# Arduino_uno_sch.net
KiCad netlist of a schematic drawn in Altium Designer
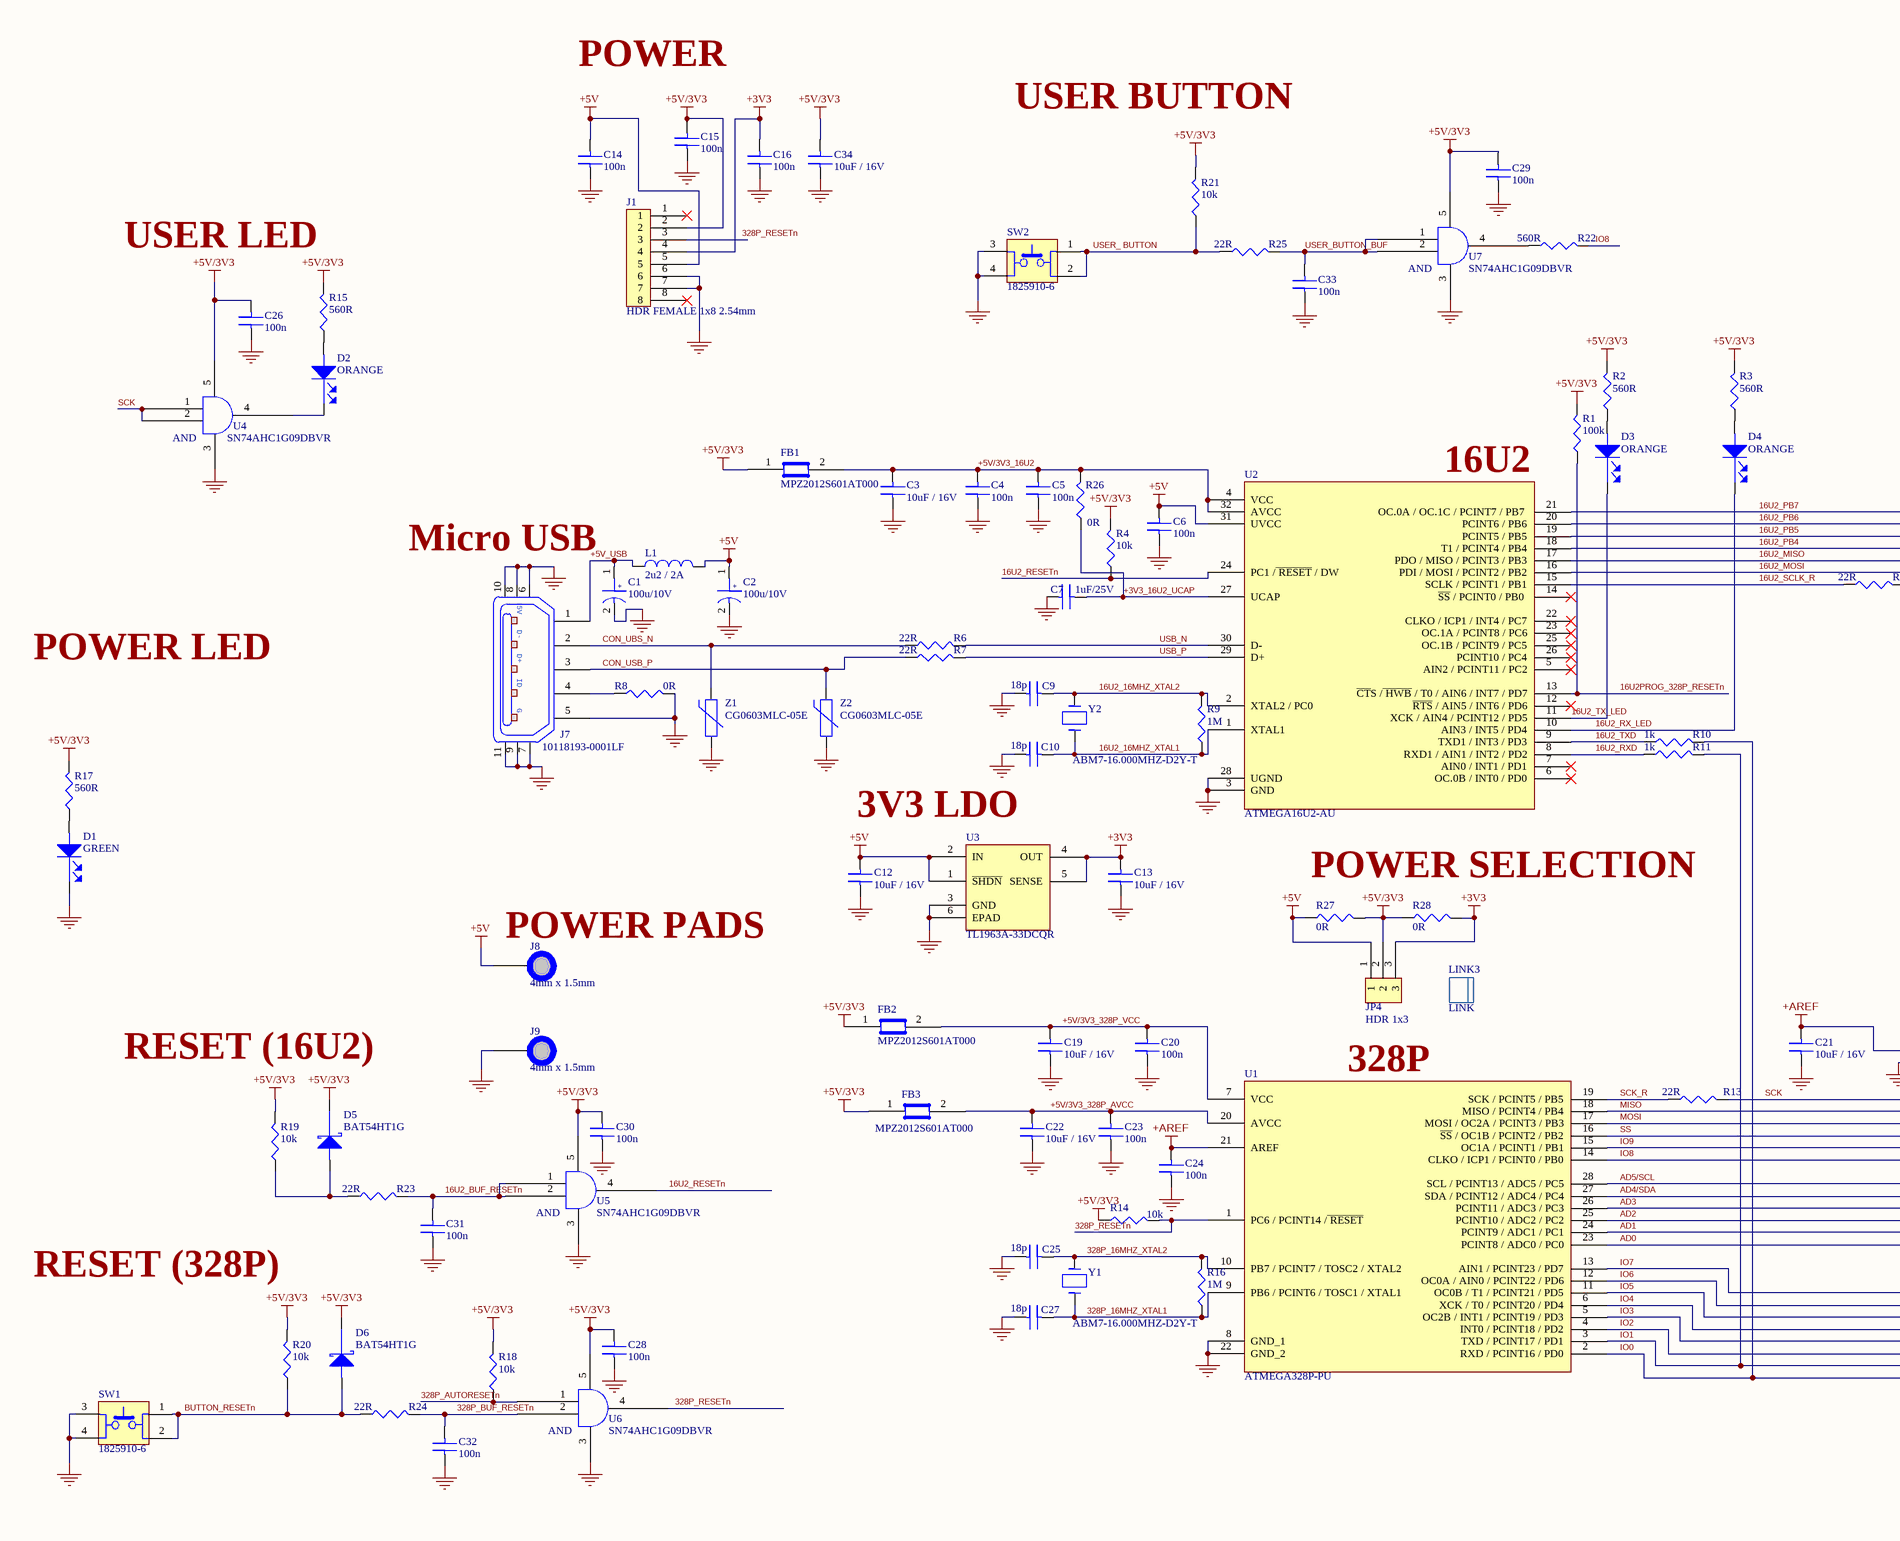
[diagram p0: Arduino_uno_sch.SchDoc, left]
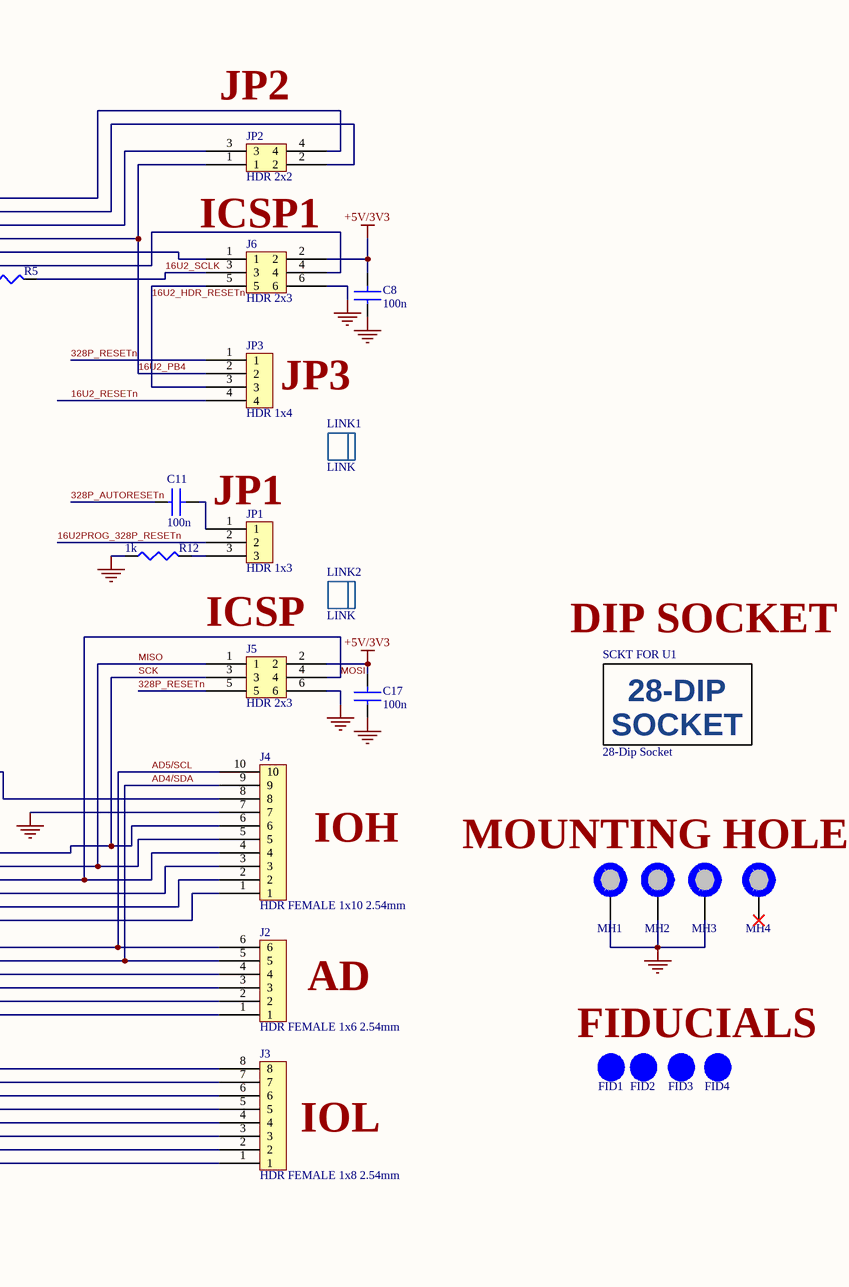
[diagram p1: Arduino_uno_sch.SchDoc, right]

(export (version "E")
  (design (tool "Eeschema 10.0.6"))
  (components
    (comp (ref "C1")
      (value "100u/10V")
      (footprint "C_ALU_C_SIZE")
      (description "Cap Aluminum 100uF 10V 20% (5 X 5.4mm) SMD 50mA 1000 hr 85°C T/R")
      (fields
        (field (name "MANUFACTURER") "Panasonic")
        (field (name "MANUFACTURER PART NUMBER") "EEE-1AA101WR")
      )
      (libsource (lib "Arduino_Schlib1") (part "EEE-1AA101WR"))
    )
    (comp (ref "C2")
      (value "100u/10V")
      (footprint "C_ALU_C_SIZE")
      (description "Cap Aluminum 100uF 10V 20% (5 X 5.4mm) SMD 50mA 1000 hr 85°C T/R")
      (fields
        (field (name "MANUFACTURER") "Panasonic")
        (field (name "MANUFACTURER PART NUMBER") "EEE-1AA101WR")
      )
      (libsource (lib "Arduino_Schlib1") (part "EEE-1AA101WR"))
    )
    (comp (ref "C3")
      (value "10uF / 16V")
      (footprint "C0805")
      (fields
        (field (name "MANUFACTURER") "TDK")
        (field (name "MANUFACTURER PART NUMBER") "C2012X5R1C106M125AC")
        (field (name "TOLERANCE") "20%")
      )
      (libsource (lib "Arduino_Schlib1") (part "C2012X5R1C106M125AC"))
    )
    (comp (ref "C4")
      (value "100n")
      (footprint "C0805")
      (fields
        (field (name "MANUFACTURER") "TDK")
        (field (name "MANUFACTURER PART NUMBER") "C2012X7R1H104K085AA")
        (field (name "TOLERANCE") "10%")
      )
      (libsource (lib "Arduino_Schlib1") (part "C2012X7R1H104K085AA"))
    )
    (comp (ref "C5")
      (value "100n")
      (footprint "C0805")
      (fields
        (field (name "MANUFACTURER") "TDK")
        (field (name "MANUFACTURER PART NUMBER") "C2012X7R1H104K085AA")
        (field (name "TOLERANCE") "10%")
      )
      (libsource (lib "Arduino_Schlib1") (part "C2012X7R1H104K085AA"))
    )
    (comp (ref "C6")
      (value "100n")
      (footprint "C0805")
      (fields
        (field (name "MANUFACTURER") "TDK")
        (field (name "MANUFACTURER PART NUMBER") "C2012X7R1H104K085AA")
        (field (name "TOLERANCE") "10%")
      )
      (libsource (lib "Arduino_Schlib1") (part "C2012X7R1H104K085AA"))
    )
    (comp (ref "C7")
      (value "1uF/25V")
      (footprint "C0805")
      (fields
        (field (name "MANUFACTURER") "TDK")
        (field (name "MANUFACTURER PART NUMBER") "C2012X5R1E105K125AA")
        (field (name "VOLTAGE") "25V")
      )
      (libsource (lib "Arduino_Schlib1") (part "C2012X5R1E105K125AA"))
    )
    (comp (ref "C8")
      (value "100n")
      (footprint "C0805")
      (fields
        (field (name "MANUFACTURER") "TDK")
        (field (name "MANUFACTURER PART NUMBER") "C2012X7R1H104K085AA")
        (field (name "TOLERANCE") "10%")
      )
      (libsource (lib "Arduino_Schlib1") (part "C2012X7R1H104K085AA"))
    )
    (comp (ref "C9")
      (value "18p")
      (footprint "C0805")
      (description "CAP CER 18PF 50V C0G/NP0 0805")
      (fields
        (field (name "MANUFACTURER") "KEMET")
        (field (name "MANUFACTURER PART NUMBER") "C0805C180J5GACTU")
      )
      (libsource (lib "Arduino_Schlib1") (part "C0805C180J5GACTU"))
    )
    (comp (ref "C10")
      (value "18p")
      (footprint "C0805")
      (description "CAP CER 18PF 50V C0G/NP0 0805")
      (fields
        (field (name "MANUFACTURER") "KEMET")
        (field (name "MANUFACTURER PART NUMBER") "C0805C180J5GACTU")
      )
      (libsource (lib "Arduino_Schlib1") (part "C0805C180J5GACTU"))
    )
    (comp (ref "C11")
      (value "100n")
      (footprint "C0805")
      (fields
        (field (name "MANUFACTURER") "TDK")
        (field (name "MANUFACTURER PART NUMBER") "C2012X7R1H104K085AA")
        (field (name "TOLERANCE") "10%")
      )
      (libsource (lib "Arduino_Schlib1") (part "C2012X7R1H104K085AA"))
    )
    (comp (ref "C12")
      (value "10uF / 16V")
      (footprint "C0805")
      (fields
        (field (name "MANUFACTURER") "TDK")
        (field (name "MANUFACTURER PART NUMBER") "C2012X5R1C106M125AC")
        (field (name "TOLERANCE") "20%")
      )
      (libsource (lib "Arduino_Schlib1") (part "C2012X5R1C106M125AC"))
    )
    (comp (ref "C13")
      (value "10uF / 16V")
      (footprint "C0805")
      (fields
        (field (name "MANUFACTURER") "TDK")
        (field (name "MANUFACTURER PART NUMBER") "C2012X5R1C106M125AC")
        (field (name "TOLERANCE") "20%")
      )
      (libsource (lib "Arduino_Schlib1") (part "C2012X5R1C106M125AC"))
    )
    (comp (ref "C14")
      (value "100n")
      (footprint "C0805")
      (fields
        (field (name "MANUFACTURER") "TDK")
        (field (name "MANUFACTURER PART NUMBER") "C2012X7R1H104K085AA")
        (field (name "TOLERANCE") "10%")
      )
      (libsource (lib "Arduino_Schlib1") (part "C2012X7R1H104K085AA"))
    )
    (comp (ref "C15")
      (value "100n")
      (footprint "C0805")
      (fields
        (field (name "MANUFACTURER") "TDK")
        (field (name "MANUFACTURER PART NUMBER") "C2012X7R1H104K085AA")
        (field (name "TOLERANCE") "10%")
      )
      (libsource (lib "Arduino_Schlib1") (part "C2012X7R1H104K085AA"))
    )
    (comp (ref "C16")
      (value "100n")
      (footprint "C0805")
      (fields
        (field (name "MANUFACTURER") "TDK")
        (field (name "MANUFACTURER PART NUMBER") "C2012X7R1H104K085AA")
        (field (name "TOLERANCE") "10%")
      )
      (libsource (lib "Arduino_Schlib1") (part "C2012X7R1H104K085AA"))
    )
    (comp (ref "C17")
      (value "100n")
      (footprint "C0805")
      (fields
        (field (name "MANUFACTURER") "TDK")
        (field (name "MANUFACTURER PART NUMBER") "C2012X7R1H104K085AA")
        (field (name "TOLERANCE") "10%")
      )
      (libsource (lib "Arduino_Schlib1") (part "C2012X7R1H104K085AA"))
    )
    (comp (ref "C19")
      (value "10uF / 16V")
      (footprint "C0805")
      (fields
        (field (name "MANUFACTURER") "TDK")
        (field (name "MANUFACTURER PART NUMBER") "C2012X5R1C106M125AC")
        (field (name "TOLERANCE") "20%")
      )
      (libsource (lib "Arduino_Schlib1") (part "C2012X5R1C106M125AC"))
    )
    (comp (ref "C20")
      (value "100n")
      (footprint "C0805")
      (fields
        (field (name "MANUFACTURER") "TDK")
        (field (name "MANUFACTURER PART NUMBER") "C2012X7R1H104K085AA")
        (field (name "TOLERANCE") "10%")
      )
      (libsource (lib "Arduino_Schlib1") (part "C2012X7R1H104K085AA"))
    )
    (comp (ref "C21")
      (value "10uF / 16V")
      (footprint "C0805")
      (fields
        (field (name "MANUFACTURER") "TDK")
        (field (name "MANUFACTURER PART NUMBER") "C2012X5R1C106M125AC")
        (field (name "TOLERANCE") "20%")
      )
      (libsource (lib "Arduino_Schlib1") (part "C2012X5R1C106M125AC"))
    )
    (comp (ref "C22")
      (value "10uF / 16V")
      (footprint "C0805")
      (fields
        (field (name "MANUFACTURER") "TDK")
        (field (name "MANUFACTURER PART NUMBER") "C2012X5R1C106M125AC")
        (field (name "TOLERANCE") "20%")
      )
      (libsource (lib "Arduino_Schlib1") (part "C2012X5R1C106M125AC"))
    )
    (comp (ref "C23")
      (value "100n")
      (footprint "C0805")
      (fields
        (field (name "MANUFACTURER") "TDK")
        (field (name "MANUFACTURER PART NUMBER") "C2012X7R1H104K085AA")
        (field (name "TOLERANCE") "10%")
      )
      (libsource (lib "Arduino_Schlib1") (part "C2012X7R1H104K085AA"))
    )
    (comp (ref "C24")
      (value "100n")
      (footprint "C0805")
      (fields
        (field (name "MANUFACTURER") "TDK")
        (field (name "MANUFACTURER PART NUMBER") "C2012X7R1H104K085AA")
        (field (name "TOLERANCE") "10%")
      )
      (libsource (lib "Arduino_Schlib1") (part "C2012X7R1H104K085AA"))
    )
    (comp (ref "C25")
      (value "18p")
      (footprint "C0805")
      (description "CAP CER 18PF 50V C0G/NP0 0805")
      (fields
        (field (name "MANUFACTURER") "KEMET")
        (field (name "MANUFACTURER PART NUMBER") "C0805C180J5GACTU")
      )
      (libsource (lib "Arduino_Schlib1") (part "C0805C180J5GACTU"))
    )
    (comp (ref "C26")
      (value "100n")
      (footprint "C0805")
      (fields
        (field (name "MANUFACTURER") "TDK")
        (field (name "MANUFACTURER PART NUMBER") "C2012X7R1H104K085AA")
        (field (name "TOLERANCE") "10%")
      )
      (libsource (lib "Arduino_Schlib1") (part "C2012X7R1H104K085AA"))
    )
    (comp (ref "C27")
      (value "18p")
      (footprint "C0805")
      (description "CAP CER 18PF 50V C0G/NP0 0805")
      (fields
        (field (name "MANUFACTURER") "KEMET")
        (field (name "MANUFACTURER PART NUMBER") "C0805C180J5GACTU")
      )
      (libsource (lib "Arduino_Schlib1") (part "C0805C180J5GACTU"))
    )
    (comp (ref "C28")
      (value "100n")
      (footprint "C0805")
      (fields
        (field (name "MANUFACTURER") "TDK")
        (field (name "MANUFACTURER PART NUMBER") "C2012X7R1H104K085AA")
        (field (name "TOLERANCE") "10%")
      )
      (libsource (lib "Arduino_Schlib1") (part "C2012X7R1H104K085AA"))
    )
    (comp (ref "C29")
      (value "100n")
      (footprint "C0805")
      (fields
        (field (name "MANUFACTURER") "TDK")
        (field (name "MANUFACTURER PART NUMBER") "C2012X7R1H104K085AA")
        (field (name "TOLERANCE") "10%")
      )
      (libsource (lib "Arduino_Schlib1") (part "C2012X7R1H104K085AA"))
    )
    (comp (ref "C30")
      (value "100n")
      (footprint "C0805")
      (fields
        (field (name "MANUFACTURER") "TDK")
        (field (name "MANUFACTURER PART NUMBER") "C2012X7R1H104K085AA")
        (field (name "TOLERANCE") "10%")
      )
      (libsource (lib "Arduino_Schlib1") (part "C2012X7R1H104K085AA"))
    )
    (comp (ref "C31")
      (value "100n")
      (footprint "C0805")
      (fields
        (field (name "MANUFACTURER") "TDK")
        (field (name "MANUFACTURER PART NUMBER") "C2012X7R1H104K085AA")
        (field (name "TOLERANCE") "10%")
      )
      (libsource (lib "Arduino_Schlib1") (part "C2012X7R1H104K085AA"))
    )
    (comp (ref "C32")
      (value "100n")
      (footprint "C0805")
      (fields
        (field (name "MANUFACTURER") "TDK")
        (field (name "MANUFACTURER PART NUMBER") "C2012X7R1H104K085AA")
        (field (name "TOLERANCE") "10%")
      )
      (libsource (lib "Arduino_Schlib1") (part "C2012X7R1H104K085AA"))
    )
    (comp (ref "C33")
      (value "100n")
      (footprint "C0805")
      (fields
        (field (name "MANUFACTURER") "TDK")
        (field (name "MANUFACTURER PART NUMBER") "C2012X7R1H104K085AA")
        (field (name "TOLERANCE") "10%")
      )
      (libsource (lib "Arduino_Schlib1") (part "C2012X7R1H104K085AA"))
    )
    (comp (ref "C34")
      (value "10uF / 16V")
      (footprint "C0805")
      (fields
        (field (name "MANUFACTURER") "TDK")
        (field (name "MANUFACTURER PART NUMBER") "C2012X5R1C106M125AC")
        (field (name "TOLERANCE") "20%")
      )
      (libsource (lib "Arduino_Schlib1") (part "C2012X5R1C106M125AC"))
    )
    (comp (ref "D1")
      (value "GREEN")
      (footprint "LED0603")
      (description "LED Uni-Color Green 572nm 2-Pin Chip 0603(1608Metric) T/R")
      (fields
        (field (name "MANUFACTURER") "Osram Opto")
        (field (name "MANUFACTURER PART NUMBER") "LGL29K-G2J1-24-Z")
      )
      (libsource (lib "Arduino_Schlib1") (part "LGL29K-G2J1-24-Z"))
    )
    (comp (ref "D2")
      (value "ORANGE")
      (footprint "LED0603")
      (description "OSRAM - LO L29K-H2K1-24-Z - SMARTLED 0603 ORANGE")
      (fields
        (field (name "MANUFACTURER") "Osram Opto")
        (field (name "MANUFACTURER PART NUMBER") "LOL29K-H2K1-24-Z")
      )
      (libsource (lib "Arduino_Schlib1") (part "LOL29K-H2K1-24-Z"))
    )
    (comp (ref "D3")
      (value "ORANGE")
      (footprint "LED0603")
      (description "OSRAM - LO L29K-H2K1-24-Z - SMARTLED 0603 ORANGE")
      (fields
        (field (name "MANUFACTURER") "Osram Opto")
        (field (name "MANUFACTURER PART NUMBER") "LOL29K-H2K1-24-Z")
      )
      (libsource (lib "Arduino_Schlib1") (part "LOL29K-H2K1-24-Z"))
    )
    (comp (ref "D4")
      (value "ORANGE")
      (footprint "LED0603")
      (description "OSRAM - LO L29K-H2K1-24-Z - SMARTLED 0603 ORANGE")
      (fields
        (field (name "MANUFACTURER") "Osram Opto")
        (field (name "MANUFACTURER PART NUMBER") "LOL29K-H2K1-24-Z")
      )
      (libsource (lib "Arduino_Schlib1") (part "LOL29K-H2K1-24-Z"))
    )
    (comp (ref "D5")
      (value "BAT54HT1G")
      (footprint "SOD323")
      (description "Small Signal Schottky Diode, Single, 30 V, 200 mA, 800 mV, 600 mA, 150 C ;RoHS Compliant: Yes")
      (fields (field (name "MANUFACTURER") "ON Semiconductor / Fairchild"))
      (libsource (lib "Arduino_Schlib1") (part "BAT54HT1G"))
    )
    (comp (ref "D6")
      (value "BAT54HT1G")
      (footprint "SOD323")
      (description "Small Signal Schottky Diode, Single, 30 V, 200 mA, 800 mV, 600 mA, 150 C ;RoHS Compliant: Yes")
      (fields (field (name "MANUFACTURER") "ON Semiconductor / Fairchild"))
      (libsource (lib "Arduino_Schlib1") (part "BAT54HT1G"))
    )
    (comp (ref "FB1")
      (value "MPZ2012S601AT000")
      (footprint "C0805")
      (description "FERRITE BEAD 600 OHM 0805 1LN")
      (fields (field (name "MANUFACTURER") "TDK"))
      (libsource (lib "Arduino_Schlib1") (part "MPZ2012S601AT000"))
    )
    (comp (ref "FB2")
      (value "MPZ2012S601AT000")
      (footprint "C0805")
      (description "FERRITE BEAD 600 OHM 0805 1LN")
      (fields (field (name "MANUFACTURER") "TDK"))
      (libsource (lib "Arduino_Schlib1") (part "MPZ2012S601AT000"))
    )
    (comp (ref "FB3")
      (value "MPZ2012S601AT000")
      (footprint "C0805")
      (description "FERRITE BEAD 600 OHM 0805 1LN")
      (fields (field (name "MANUFACTURER") "TDK"))
      (libsource (lib "Arduino_Schlib1") (part "MPZ2012S601AT000"))
    )
    (comp (ref "FID1")
      (value "FID_1MMC")
      (footprint "FID _40X120D")
      (description "Fiducial 40 mil diameter, 120 mil mask")
      (libsource (lib "Arduino_Schlib1") (part "FID_1MMC"))
    )
    (comp (ref "FID2")
      (value "FID_1MMC")
      (footprint "FID _40X120D")
      (description "Fiducial 40 mil diameter, 120 mil mask")
      (libsource (lib "Arduino_Schlib1") (part "FID_1MMC"))
    )
    (comp (ref "FID3")
      (value "FID_1MMC")
      (footprint "FID _40X120D")
      (description "Fiducial 40 mil diameter, 120 mil mask")
      (libsource (lib "Arduino_Schlib1") (part "FID_1MMC"))
    )
    (comp (ref "FID4")
      (value "FID_1MMC")
      (footprint "FID _40X120D")
      (description "Fiducial 40 mil diameter, 120 mil mask")
      (libsource (lib "Arduino_Schlib1") (part "FID_1MMC"))
    )
    (comp (ref "J1")
      (value "HDR FEMALE 1x8 2.54mm")
      (footprint "Hdr_Female_1x8_2.54mm")
      (description "2.54mm (0.1\") Pitch SIL Vertical PC Tail Socket Assembly, selective gold + tin, 8 contacts")
      (fields (field (name "MANUFACTURER") "Harwin") (field (name "MANUFACTURER PART NUMBER") "M20-7820842"))
      (libsource (lib "") (part "M20-7820842_1"))
    )
    (comp (ref "J2")
      (value "HDR FEMALE 1x6 2.54mm")
      (footprint "Hdr_Female_1x6_2.54mm")
      (description "06-WAY SIL VERT SOCKET L/FREE")
      (fields (field (name "MANUFACTURER") "Harwin") (field (name "MANUFACTURER PART NUMBER") "M20-7820646"))
      (libsource (lib "Arduino_Schlib1") (part "M20-7820646"))
    )
    (comp (ref "J3")
      (value "HDR FEMALE 1x8 2.54mm")
      (footprint "Hdr_Female_1x8_2.54mm")
      (description "2.54mm (0.1\") Pitch SIL Vertical PC Tail Socket Assembly, selective gold + tin, 8 contacts")
      (fields (field (name "MANUFACTURER") "Harwin") (field (name "MANUFACTURER PART NUMBER") "M20-7820842"))
      (libsource (lib "Arduino_Schlib1") (part "M20-7820842"))
    )
    (comp (ref "J4")
      (value "HDR FEMALE 1x10 2.54mm")
      (footprint "Hdr_Female_1x10_2.54mm")
      (fields (field (name "MANUFACTURER") "Harwin") (field (name "MANUFACTURER PART NUMBER") "M20-7821046"))
      (libsource (lib "Arduino_Schlib1") (part "M20-7821046"))
    )
    (comp (ref "J5")
      (value "HDR 2x3")
      (footprint "HDR_2x3_2.54mm")
      (description "CONN HEADER 6POS .100 STR 30AU")
      (fields
        (field (name "MANUFACTURER") "Amphenol FCI")
        (field (name "MANUFACTURER PART NUMBER") "67997-106HLF")
      )
      (libsource (lib "Arduino_Schlib1") (part "67997-106HLF"))
    )
    (comp (ref "J6")
      (value "HDR 2x3")
      (footprint "HDR_2x3_2.54mm")
      (description "CONN HEADER 6POS .100 STR 30AU")
      (fields
        (field (name "MANUFACTURER") "Amphenol FCI")
        (field (name "MANUFACTURER PART NUMBER") "67997-106HLF")
      )
      (libsource (lib "Arduino_Schlib1") (part "67997-106HLF"))
    )
    (comp (ref "J7")
      (value "10118193-0001LF")
      (footprint "10118193")
      (description "CONN USB MICRO B RECPT SMT R/A")
      (fields (field (name "MANUFACTURER") "Amphenol FCI"))
      (libsource (lib "Arduino_Schlib1") (part "10118193-0001LF"))
    )
    (comp (ref "J8")
      (value "4mm x 1.5mm")
      (footprint "PAD_WITH_HOLE_4mm x 1.5mm")
      (description "Pad with a hole 4mm x 1.5mm")
      (libsource (lib "Arduino_Schlib1") (part "PAD_WITH_HOLE_4MMX1.5MM"))
    )
    (comp (ref "J9")
      (value "4mm x 1.5mm")
      (footprint "PAD_WITH_HOLE_4mm x 1.5mm")
      (description "Pad with a hole 4mm x 1.5mm")
      (libsource (lib "Arduino_Schlib1") (part "PAD_WITH_HOLE_4MMX1.5MM"))
    )
    (comp (ref "JP1")
      (value "HDR 1x3")
      (footprint "Hdr_Female_1x3_2.54mm")
      (description "Conn Unshrouded Header HDR 3 POS 2.54mm Solder ST Thru-Hole Bulk")
      (fields
        (field (name "MANUFACTURER") "Amphenol FCI")
        (field (name "MANUFACTURER PART NUMBER") "68000-103HLF")
      )
      (libsource (lib "Arduino_Schlib1") (part "68000-103HLF"))
    )
    (comp (ref "JP2")
      (value "HDR 2x2")
      (footprint "HDR_2x2_2.54mm")
      (description "CONN HEADER VERT 4POS 2.54MM")
      (fields
        (field (name "MANUFACTURER") "Amphenol FCI")
        (field (name "MANUFACTURER PART NUMBER") "68602-204HLF")
      )
      (libsource (lib "Arduino_Schlib1") (part "68602-204HLF"))
    )
    (comp (ref "JP3")
      (value "HDR 1x4")
      (footprint "Hdr_Female_1x4_2.54mm")
      (description "CONN HEADER VERT 4POS 2.54MM")
      (fields
        (field (name "MANUFACTURER") "Amphenol FCI")
        (field (name "MANUFACTURER PART NUMBER") "68001-204HLF")
      )
      (libsource (lib "Arduino_Schlib1") (part "68001-204HLF"))
    )
    (comp (ref "JP4")
      (value "HDR 1x3")
      (footprint "Hdr_Female_1x3_2.54mm")
      (description "Conn Unshrouded Header HDR 3 POS 2.54mm Solder ST Thru-Hole Bulk")
      (fields
        (field (name "MANUFACTURER") "Amphenol FCI")
        (field (name "MANUFACTURER PART NUMBER") "68000-103HLF")
      )
      (libsource (lib "") (part "68000-103HLF_1"))
    )
    (comp (ref "L1")
      (value "2u2 / 2A")
      (footprint "CL210_IND")
      (description "FIXED IND 2.2UH 2A 80 MOHM SMD")
      (fields
        (field (name "MANUFACTURER") "KEMET")
        (field (name "MANUFACTURER PART NUMBER") "L1210R2R2MDWIT")
      )
      (libsource (lib "Arduino_Schlib1") (part "L1210R2R2MDWIT"))
    )
    (comp (ref "LINK1")
      (value "LINK")
      (description "CONN JUMPER SHORTING .100\" GOLD")
      (fields
        (field (name "MANUFACTURER") "Sullins")
        (field (name "MANUFACTURER PART NUMBER") "QPC02SXGN-RC")
      )
      (libsource (lib "Arduino_Schlib1") (part "QPC02SXGN-RC"))
    )
    (comp (ref "LINK2")
      (value "LINK")
      (description "CONN JUMPER SHORTING .100\" GOLD")
      (fields
        (field (name "MANUFACTURER") "Sullins")
        (field (name "MANUFACTURER PART NUMBER") "QPC02SXGN-RC")
      )
      (libsource (lib "Arduino_Schlib1") (part "QPC02SXGN-RC"))
    )
    (comp (ref "LINK3")
      (value "LINK")
      (description "CONN JUMPER SHORTING .100\" GOLD")
      (fields
        (field (name "MANUFACTURER") "Sullins")
        (field (name "MANUFACTURER PART NUMBER") "QPC02SXGN-RC")
      )
      (libsource (lib "Arduino_Schlib1") (part "QPC02SXGN-RC"))
    )
    (comp (ref "MH1")
      (value "MH_7.4MMNC_3.2MMND")
      (footprint "MH_7.4MMNC_3.2MMND")
      (description "Hole 7.4mm diameter (Non copper) , 3.2mm drill NPTH")
      (libsource (lib "Arduino_Schlib1") (part "MH_7.4MMNC_3.2MMND"))
    )
    (comp (ref "MH2")
      (value "MH_7.4MMNC_3.2MMND")
      (footprint "MH_7.4MMNC_3.2MMND")
      (description "Hole 7.4mm diameter (Non copper) , 3.2mm drill NPTH")
      (libsource (lib "Arduino_Schlib1") (part "MH_7.4MMNC_3.2MMND"))
    )
    (comp (ref "MH3")
      (value "MH_7.4MMNC_3.2MMND")
      (footprint "MH_7.4MMNC_3.2MMND")
      (description "Hole 7.4mm diameter (Non copper) , 3.2mm drill NPTH")
      (libsource (lib "Arduino_Schlib1") (part "MH_7.4MMNC_3.2MMND"))
    )
    (comp (ref "MH4")
      (value "MH_7.4MMNC_3.2MMND")
      (footprint "MH_7.4MMNC_3.2MMND")
      (description "Hole 7.4mm diameter (Non copper) , 3.2mm drill NPTH")
      (libsource (lib "Arduino_Schlib1") (part "MH_7.4MMNC_3.2MMND"))
    )
    (comp (ref "R1")
      (value "100k")
      (footprint "R0805")
      (description "YAGEO         RC0805FR-07100KL            RES, THICK FILM, 100K, 1%, 0.125W, 0805, REEL")
      (fields
        (field (name "MANUFACTURER") "Yageo")
        (field (name "MANUFACTURER PART NUMBER") "RC0805FR-07100KL")
      )
      (libsource (lib "Arduino_Schlib1") (part "RC0805FR-07100KL"))
    )
    (comp (ref "R2")
      (value "560R")
      (footprint "R0805")
      (description "Surface Mount Thick Film Resistor, RC Series, 560 ohm, 125 mW, - 1%, 150 V, 0805 [2012 Metric]")
      (fields
        (field (name "MANUFACTURER") "Yageo")
        (field (name "MANUFACTURER PART NUMBER") "RC0805FR-07560RL")
      )
      (libsource (lib "Arduino_Schlib1") (part "RC0805FR-07560RL"))
    )
    (comp (ref "R3")
      (value "560R")
      (footprint "R0805")
      (description "Surface Mount Thick Film Resistor, RC Series, 560 ohm, 125 mW, - 1%, 150 V, 0805 [2012 Metric]")
      (fields
        (field (name "MANUFACTURER") "Yageo")
        (field (name "MANUFACTURER PART NUMBER") "RC0805FR-07560RL")
      )
      (libsource (lib "Arduino_Schlib1") (part "RC0805FR-07560RL"))
    )
    (comp (ref "R4")
      (value "10k")
      (footprint "R0805")
      (description "RES SMD 10K OHM 1% 1/8W 0805")
      (fields
        (field (name "MANUFACTURER") "Yageo")
        (field (name "MANUFACTURER PART NUMBER") "RC0805FR-0710KL")
      )
      (libsource (lib "Arduino_Schlib1") (part "RC0805FR-0710KL"))
    )
    (comp (ref "R5")
      (value "22R")
      (footprint "R0805")
      (description "RES SMD 22 OHM 1% 1/8W 0805")
      (fields
        (field (name "MANUFACTURER") "Yageo")
        (field (name "MANUFACTURER PART NUMBER") "RC0805FR-0722RL")
      )
      (libsource (lib "Arduino_Schlib1") (part "RC0805FR-0722RL"))
    )
    (comp (ref "R6")
      (value "22R")
      (footprint "R0805")
      (description "RES SMD 22 OHM 1% 1/8W 0805")
      (fields
        (field (name "MANUFACTURER") "Yageo")
        (field (name "MANUFACTURER PART NUMBER") "RC0805FR-0722RL")
      )
      (libsource (lib "Arduino_Schlib1") (part "RC0805FR-0722RL"))
    )
    (comp (ref "R7")
      (value "22R")
      (footprint "R0805")
      (description "RES SMD 22 OHM 1% 1/8W 0805")
      (fields
        (field (name "MANUFACTURER") "Yageo")
        (field (name "MANUFACTURER PART NUMBER") "RC0805FR-0722RL")
      )
      (libsource (lib "Arduino_Schlib1") (part "RC0805FR-0722RL"))
    )
    (comp (ref "R8")
      (value "0R")
      (footprint "R0805")
      (description "Surface Mount Thick Film Resistor, RC Series, 125 mW, - 5%, 150 V, 0805 [2012 Metric]")
      (fields
        (field (name "MANUFACTURER") "Yageo")
        (field (name "MANUFACTURER PART NUMBER") "RC0805JR-070RL")
      )
      (libsource (lib "Arduino_Schlib1") (part "RC0805JR-070RL"))
    )
    (comp (ref "R9")
      (value "1M")
      (footprint "R0805")
      (description "RES SMD 1M OHM 1% 1/8W 0805")
      (fields
        (field (name "MANUFACTURER") "Yageo")
        (field (name "MANUFACTURER PART NUMBER") "RC0805FR-071ML")
      )
      (libsource (lib "Arduino_Schlib1") (part "RC0805FR-071ML"))
    )
    (comp (ref "R10")
      (value "1k")
      (footprint "R0805")
      (fields
        (field (name "MANUFACTURER") "Yageo")
        (field (name "MANUFACTURER PART NUMBER") "RC0805FR-071KL")
        (field (name "TOLERANCE") "1%")
      )
      (libsource (lib "Arduino_Schlib1") (part "RC0805FR-071KL"))
    )
    (comp (ref "R11")
      (value "1k")
      (footprint "R0805")
      (fields
        (field (name "MANUFACTURER") "Yageo")
        (field (name "MANUFACTURER PART NUMBER") "RC0805FR-071KL")
        (field (name "TOLERANCE") "1%")
      )
      (libsource (lib "Arduino_Schlib1") (part "RC0805FR-071KL"))
    )
    (comp (ref "R12")
      (value "1k")
      (footprint "R0805")
      (fields
        (field (name "MANUFACTURER") "Yageo")
        (field (name "MANUFACTURER PART NUMBER") "RC0805FR-071KL")
        (field (name "TOLERANCE") "1%")
      )
      (libsource (lib "Arduino_Schlib1") (part "RC0805FR-071KL"))
    )
    (comp (ref "R13")
      (value "22R")
      (footprint "R0805")
      (description "RES SMD 22 OHM 1% 1/8W 0805")
      (fields
        (field (name "MANUFACTURER") "Yageo")
        (field (name "MANUFACTURER PART NUMBER") "RC0805FR-0722RL")
      )
      (libsource (lib "Arduino_Schlib1") (part "RC0805FR-0722RL"))
    )
    (comp (ref "R14")
      (value "10k")
      (footprint "R0805")
      (description "RES SMD 10K OHM 1% 1/8W 0805")
      (fields
        (field (name "MANUFACTURER") "Yageo")
        (field (name "MANUFACTURER PART NUMBER") "RC0805FR-0710KL")
      )
      (libsource (lib "Arduino_Schlib1") (part "RC0805FR-0710KL"))
    )
    (comp (ref "R15")
      (value "560R")
      (footprint "R0805")
      (description "Surface Mount Thick Film Resistor, RC Series, 560 ohm, 125 mW, - 1%, 150 V, 0805 [2012 Metric]")
      (fields
        (field (name "MANUFACTURER") "Yageo")
        (field (name "MANUFACTURER PART NUMBER") "RC0805FR-07560RL")
      )
      (libsource (lib "Arduino_Schlib1") (part "RC0805FR-07560RL"))
    )
    (comp (ref "R16")
      (value "1M")
      (footprint "R0805")
      (description "RES SMD 1M OHM 1% 1/8W 0805")
      (fields
        (field (name "MANUFACTURER") "Yageo")
        (field (name "MANUFACTURER PART NUMBER") "RC0805FR-071ML")
      )
      (libsource (lib "Arduino_Schlib1") (part "RC0805FR-071ML"))
    )
    (comp (ref "R17")
      (value "560R")
      (footprint "R0805")
      (description "Surface Mount Thick Film Resistor, RC Series, 560 ohm, 125 mW, - 1%, 150 V, 0805 [2012 Metric]")
      (fields
        (field (name "MANUFACTURER") "Yageo")
        (field (name "MANUFACTURER PART NUMBER") "RC0805FR-07560RL")
      )
      (libsource (lib "Arduino_Schlib1") (part "RC0805FR-07560RL"))
    )
    (comp (ref "R18")
      (value "10k")
      (footprint "R0805")
      (description "RES SMD 10K OHM 1% 1/8W 0805")
      (fields
        (field (name "MANUFACTURER") "Yageo")
        (field (name "MANUFACTURER PART NUMBER") "RC0805FR-0710KL")
      )
      (libsource (lib "Arduino_Schlib1") (part "RC0805FR-0710KL"))
    )
    (comp (ref "R19")
      (value "10k")
      (footprint "R0805")
      (description "RES SMD 10K OHM 1% 1/8W 0805")
      (fields
        (field (name "MANUFACTURER") "Yageo")
        (field (name "MANUFACTURER PART NUMBER") "RC0805FR-0710KL")
      )
      (libsource (lib "Arduino_Schlib1") (part "RC0805FR-0710KL"))
    )
    (comp (ref "R20")
      (value "10k")
      (footprint "R0805")
      (description "RES SMD 10K OHM 1% 1/8W 0805")
      (fields
        (field (name "MANUFACTURER") "Yageo")
        (field (name "MANUFACTURER PART NUMBER") "RC0805FR-0710KL")
      )
      (libsource (lib "Arduino_Schlib1") (part "RC0805FR-0710KL"))
    )
    (comp (ref "R21")
      (value "10k")
      (footprint "R0805")
      (description "RES SMD 10K OHM 1% 1/8W 0805")
      (fields
        (field (name "MANUFACTURER") "Yageo")
        (field (name "MANUFACTURER PART NUMBER") "RC0805FR-0710KL")
      )
      (libsource (lib "Arduino_Schlib1") (part "RC0805FR-0710KL"))
    )
    (comp (ref "R22")
      (value "560R")
      (footprint "R0805")
      (description "Surface Mount Thick Film Resistor, RC Series, 560 ohm, 125 mW, - 1%, 150 V, 0805 [2012 Metric]")
      (fields
        (field (name "MANUFACTURER") "Yageo")
        (field (name "MANUFACTURER PART NUMBER") "RC0805FR-07560RL")
      )
      (libsource (lib "Arduino_Schlib1") (part "RC0805FR-07560RL"))
    )
    (comp (ref "R23")
      (value "22R")
      (footprint "R0805")
      (description "RES SMD 22 OHM 1% 1/8W 0805")
      (fields
        (field (name "MANUFACTURER") "Yageo")
        (field (name "MANUFACTURER PART NUMBER") "RC0805FR-0722RL")
      )
      (libsource (lib "Arduino_Schlib1") (part "RC0805FR-0722RL"))
    )
    (comp (ref "R24")
      (value "22R")
      (footprint "R0805")
      (description "RES SMD 22 OHM 1% 1/8W 0805")
      (fields
        (field (name "MANUFACTURER") "Yageo")
        (field (name "MANUFACTURER PART NUMBER") "RC0805FR-0722RL")
      )
      (libsource (lib "Arduino_Schlib1") (part "RC0805FR-0722RL"))
    )
    (comp (ref "R25")
      (value "22R")
      (footprint "R0805")
      (description "RES SMD 22 OHM 1% 1/8W 0805")
      (fields
        (field (name "MANUFACTURER") "Yageo")
        (field (name "MANUFACTURER PART NUMBER") "RC0805FR-0722RL")
      )
      (libsource (lib "Arduino_Schlib1") (part "RC0805FR-0722RL"))
    )
    (comp (ref "R26")
      (value "0R")
      (footprint "R0805")
      (description "Surface Mount Thick Film Resistor, RC Series, 125 mW, - 5%, 150 V, 0805 [2012 Metric]")
      (fields
        (field (name "MANUFACTURER") "Yageo")
        (field (name "MANUFACTURER PART NUMBER") "RC0805JR-070RL")
      )
      (libsource (lib "Arduino_Schlib1") (part "RC0805JR-070RL"))
    )
    (comp (ref "R27")
      (value "0R")
      (footprint "R0805")
      (description "Surface Mount Thick Film Resistor, RC Series, 125 mW, - 5%, 150 V, 0805 [2012 Metric]")
      (fields
        (field (name "MANUFACTURER") "Yageo")
        (field (name "MANUFACTURER PART NUMBER") "RC0805JR-070RL")
      )
      (libsource (lib "Arduino_Schlib1") (part "RC0805JR-070RL"))
    )
    (comp (ref "R28")
      (value "0R")
      (footprint "R0805")
      (description "Surface Mount Thick Film Resistor, RC Series, 125 mW, - 5%, 150 V, 0805 [2012 Metric]")
      (fields
        (field (name "MANUFACTURER") "Yageo")
        (field (name "MANUFACTURER PART NUMBER") "RC0805JR-070RL")
      )
      (libsource (lib "Arduino_Schlib1") (part "RC0805JR-070RL"))
    )
    (comp (ref "SCKT FOR U1")
      (value "28-Dip Socket")
      (footprint "28_DIP_7.62mm_SOCKET")
      (description "CONN IC DIP SOCKET 28POS TIN")
      (fields (field (name "MANUFACTURER") "3M") (field (name "MANUFACTURER PART NUMBER") "4828-3004-CP"))
      (libsource (lib "Arduino_Schlib1") (part "4828-3004-CP"))
    )
    (comp (ref "SW1")
      (value "1825910-6")
      (footprint "1825910-6")
      (description "SWITCH TACTILE SPST-NO 0.05A 24V")
      (fields (field (name "MANUFACTURER") "TE Connectivity Alcoswitch"))
      (libsource (lib "Arduino_Schlib1") (part "1825910-6"))
    )
    (comp (ref "SW2")
      (value "1825910-6")
      (footprint "1825910-6")
      (description "SWITCH TACTILE SPST-NO 0.05A 24V")
      (fields (field (name "MANUFACTURER") "TE Connectivity Alcoswitch"))
      (libsource (lib "Arduino_Schlib1") (part "1825910-6"))
    )
    (comp (ref "U1")
      (value "ATMEGA328P-PU")
      (footprint "28_DIP_7.62mm")
      (description "ATMEGA328P-PU; 8 bit Microcontroller AVR 20MHz 1; 32kb Flash; 2kb RAM; I2C SPI 2")
      (fields (field (name "MANUFACTURER") "Microchip / Atmel"))
      (libsource (lib "Arduino_Schlib1") (part "ATMEGA328P-PU"))
    )
    (comp (ref "U2")
      (value "ATMEGA16U2-AU")
      (footprint "TQFP32")
      (description "MICROCHIP - ATMEGA16U2-AU - MCU, 8BIT, MEGAAVR, 16MHZ, TQFP-32")
      (fields (field (name "MANUFACTURER") "Microchip / Atmel"))
      (libsource (lib "Arduino_Schlib1") (part "ATMEGA16U2-AU"))
    )
    (comp (ref "U3")
      (value "TL1963A-33DCQR")
      (footprint "DCQ (R-PDSO-G6)")
      (description "IC REG LINEAR 3.3V 1.5A SOT223-6")
      (fields (field (name "MANUFACTURER") "Texas Instruments"))
      (libsource (lib "Arduino_Schlib1") (part "TL1963A-33DCQR"))
    )
    (comp (ref "U4")
      (value "SN74AHC1G09DBVR")
      (footprint "DBV_SOT_23_5")
      (description "TEXAS INSTRUMENTS - SN74AHC1G09DBVR - AND Gate, 74AHC1G09, 2 Input, 2 V to 5.5 V, SOT-23-5")
      (fields (field (name "MANUFACTURER") "Texas Instruments"))
      (libsource (lib "Arduino_Schlib1") (part "SN74AHC1G09DBVR"))
    )
    (comp (ref "U5")
      (value "SN74AHC1G09DBVR")
      (footprint "DBV_SOT_23_5")
      (description "TEXAS INSTRUMENTS - SN74AHC1G09DBVR - AND Gate, 74AHC1G09, 2 Input, 2 V to 5.5 V, SOT-23-5")
      (fields (field (name "MANUFACTURER") "Texas Instruments"))
      (libsource (lib "Arduino_Schlib1") (part "SN74AHC1G09DBVR"))
    )
    (comp (ref "U6")
      (value "SN74AHC1G09DBVR")
      (footprint "DBV_SOT_23_5")
      (description "TEXAS INSTRUMENTS - SN74AHC1G09DBVR - AND Gate, 74AHC1G09, 2 Input, 2 V to 5.5 V, SOT-23-5")
      (fields (field (name "MANUFACTURER") "Texas Instruments"))
      (libsource (lib "Arduino_Schlib1") (part "SN74AHC1G09DBVR"))
    )
    (comp (ref "U7")
      (value "SN74AHC1G09DBVR")
      (footprint "DBV_SOT_23_5")
      (description "TEXAS INSTRUMENTS - SN74AHC1G09DBVR - AND Gate, 74AHC1G09, 2 Input, 2 V to 5.5 V, SOT-23-5")
      (fields (field (name "MANUFACTURER") "Texas Instruments"))
      (libsource (lib "Arduino_Schlib1") (part "SN74AHC1G09DBVR"))
    )
    (comp (ref "Y1")
      (value "ABM7-16.000MHZ-D2Y-T")
      (footprint "AVM7_v1_1_BIG")
      (description "CRYSTAL 16.0000MHZ 18PF SMD")
      (fields (field (name "MANUFACTURER") "Abracon") (field (name "TOLERANCE") "20ppm"))
      (libsource (lib "Arduino_Schlib1") (part "ABM7-16.000MHZ-D2Y-T"))
    )
    (comp (ref "Y2")
      (value "ABM7-16.000MHZ-D2Y-T")
      (footprint "AVM7_v1_1_BIG")
      (description "CRYSTAL 16.0000MHZ 18PF SMD")
      (fields (field (name "MANUFACTURER") "Abracon") (field (name "TOLERANCE") "20ppm"))
      (libsource (lib "Arduino_Schlib1") (part "ABM7-16.000MHZ-D2Y-T"))
    )
    (comp (ref "Z1")
      (value "CG0603MLC-05E")
      (footprint "R0603")
      (description "VARISTOR 0603")
      (fields (field (name "MANUFACTURER") "Bourns") (field (name "VOLTAGE") "5V"))
      (libsource (lib "Arduino_Schlib1") (part "CG0603MLC-05E"))
    )
    (comp (ref "Z2")
      (value "CG0603MLC-05E")
      (footprint "R0603")
      (description "VARISTOR 0603")
      (fields (field (name "MANUFACTURER") "Bourns") (field (name "VOLTAGE") "5V"))
      (libsource (lib "Arduino_Schlib1") (part "CG0603MLC-05E"))
    )
  )
  (nets
    (net (code "1") (name "+3V3") (class "Default")
      (node (ref "C13") (pin "2") (pinfunction "2_2") (pintype "passive"))
      (node (ref "C16") (pin "2") (pinfunction "2_2") (pintype "passive"))
      (node (ref "J1") (pin "4") (pinfunction "4_4") (pintype "passive"))
      (node (ref "JP4") (pin "3") (pinfunction "3_3") (pintype "passive"))
      (node (ref "R28") (pin "2") (pinfunction "2_2") (pintype "passive"))
      (node (ref "U3") (pin "4") (pinfunction "OUT_4") (pintype "passive"))
      (node (ref "U3") (pin "5") (pinfunction "SENSE_5") (pintype "passive"))
    )
    (net (code "2") (name "+5V") (class "Default")
      (node (ref "C12") (pin "2") (pinfunction "2_2") (pintype "passive"))
      (node (ref "C14") (pin "2") (pinfunction "2_2") (pintype "passive"))
      (node (ref "C2") (pin "1") (pinfunction "1_1") (pintype "passive"))
      (node (ref "C6") (pin "2") (pinfunction "2_2") (pintype "passive"))
      (node (ref "J1") (pin "5") (pinfunction "5_5") (pintype "passive"))
      (node (ref "J8") (pin "1") (pinfunction "1_1") (pintype "passive"))
      (node (ref "JP4") (pin "1") (pinfunction "1_1") (pintype "passive"))
      (node (ref "L1") (pin "2") (pinfunction "2_2") (pintype "passive"))
      (node (ref "R27") (pin "1") (pinfunction "1_1") (pintype "passive"))
      (node (ref "U2") (pin "31") (pinfunction "UVCC_31") (pintype "passive"))
      (node (ref "U3") (pin "1") (pinfunction "~{SHDN}_1") (pintype "passive"))
      (node (ref "U3") (pin "2") (pinfunction "IN_2") (pintype "passive"))
    )
    (net (code "3") (name "+5V{slash}3V3") (class "Default")
      (node (ref "C15") (pin "2") (pinfunction "2_2") (pintype "passive"))
      (node (ref "C17") (pin "2") (pinfunction "2_2") (pintype "passive"))
      (node (ref "C26") (pin "2") (pinfunction "2_2") (pintype "passive"))
      (node (ref "C28") (pin "2") (pinfunction "2_2") (pintype "passive"))
      (node (ref "C29") (pin "2") (pinfunction "2_2") (pintype "passive"))
      (node (ref "C30") (pin "2") (pinfunction "2_2") (pintype "passive"))
      (node (ref "C34") (pin "2") (pinfunction "2_2") (pintype "passive"))
      (node (ref "C8") (pin "2") (pinfunction "2_2") (pintype "passive"))
      (node (ref "D5") (pin "1") (pinfunction "Cathode_1") (pintype "passive"))
      (node (ref "D6") (pin "1") (pinfunction "Cathode_1") (pintype "passive"))
      (node (ref "FB1") (pin "1") (pinfunction "1_1") (pintype "passive"))
      (node (ref "FB2") (pin "1") (pinfunction "1_1") (pintype "passive"))
      (node (ref "FB3") (pin "1") (pinfunction "1_1") (pintype "passive"))
      (node (ref "J1") (pin "2") (pinfunction "2_2") (pintype "passive"))
      (node (ref "J5") (pin "2") (pinfunction "2_2") (pintype "passive"))
      (node (ref "J6") (pin "2") (pinfunction "2_2") (pintype "passive"))
      (node (ref "JP4") (pin "2") (pinfunction "2_2") (pintype "passive"))
      (node (ref "R1") (pin "2") (pinfunction "2_2") (pintype "passive"))
      (node (ref "R14") (pin "1") (pinfunction "1_1") (pintype "passive"))
      (node (ref "R15") (pin "2") (pinfunction "2_2") (pintype "passive"))
      (node (ref "R17") (pin "2") (pinfunction "2_2") (pintype "passive"))
      (node (ref "R18") (pin "2") (pinfunction "2_2") (pintype "passive"))
      (node (ref "R19") (pin "2") (pinfunction "2_2") (pintype "passive"))
      (node (ref "R2") (pin "2") (pinfunction "2_2") (pintype "passive"))
      (node (ref "R20") (pin "2") (pinfunction "2_2") (pintype "passive"))
      (node (ref "R21") (pin "2") (pinfunction "2_2") (pintype "passive"))
      (node (ref "R27") (pin "2") (pinfunction "2_2") (pintype "passive"))
      (node (ref "R28") (pin "1") (pinfunction "1_1") (pintype "passive"))
      (node (ref "R3") (pin "2") (pinfunction "2_2") (pintype "passive"))
      (node (ref "R4") (pin "2") (pinfunction "2_2") (pintype "passive"))
      (node (ref "U4") (pin "5") (pinfunction "5_5") (pintype "passive"))
      (node (ref "U5") (pin "5") (pinfunction "5_5") (pintype "passive"))
      (node (ref "U6") (pin "5") (pinfunction "5_5") (pintype "passive"))
      (node (ref "U7") (pin "5") (pinfunction "5_5") (pintype "passive"))
    )
    (net (code "4") (name "+AREF") (class "Default")
      (node (ref "C21") (pin "2") (pinfunction "2_2") (pintype "passive"))
      (node (ref "C24") (pin "2") (pinfunction "2_2") (pintype "passive"))
      (node (ref "J4") (pin "8") (pinfunction "8_8") (pintype "passive"))
      (node (ref "U1") (pin "21") (pinfunction "AREF_21") (pintype "passive"))
    )
    (net (code "5") (name "/+3V3_16U2_UCAP") (class "Default")
      (node (ref "C7") (pin "2") (pinfunction "2_2") (pintype "passive"))
      (node (ref "R26") (pin "1") (pinfunction "1_1") (pintype "passive"))
      (node (ref "U2") (pin "27") (pinfunction "UCAP_27") (pintype "passive"))
    )
    (net (code "6") (name "/+5V_USB") (class "Default")
      (node (ref "C1") (pin "1") (pinfunction "1_1") (pintype "passive"))
      (node (ref "J7") (pin "1") (pinfunction "1_1") (pintype "passive"))
      (node (ref "L1") (pin "1") (pinfunction "1_1") (pintype "passive"))
    )
    (net (code "7") (name "/+5V{slash}3V3_16U2") (class "Default")
      (node (ref "C3") (pin "2") (pinfunction "2_2") (pintype "passive"))
      (node (ref "C4") (pin "2") (pinfunction "2_2") (pintype "passive"))
      (node (ref "C5") (pin "2") (pinfunction "2_2") (pintype "passive"))
      (node (ref "FB1") (pin "2") (pinfunction "2_2") (pintype "passive"))
      (node (ref "R26") (pin "2") (pinfunction "2_2") (pintype "passive"))
      (node (ref "U2") (pin "32") (pinfunction "AVCC_32") (pintype "passive"))
      (node (ref "U2") (pin "4") (pinfunction "VCC_4") (pintype "passive"))
    )
    (net (code "8") (name "/+5V{slash}3V3_328P_AVCC") (class "Default")
      (node (ref "C22") (pin "2") (pinfunction "2_2") (pintype "passive"))
      (node (ref "C23") (pin "2") (pinfunction "2_2") (pintype "passive"))
      (node (ref "FB3") (pin "2") (pinfunction "2_2") (pintype "passive"))
      (node (ref "U1") (pin "20") (pinfunction "AVCC_20") (pintype "passive"))
    )
    (net (code "9") (name "/+5V{slash}3V3_328P_VCC") (class "Default")
      (node (ref "C19") (pin "2") (pinfunction "2_2") (pintype "passive"))
      (node (ref "C20") (pin "2") (pinfunction "2_2") (pintype "passive"))
      (node (ref "FB2") (pin "2") (pinfunction "2_2") (pintype "passive"))
      (node (ref "U1") (pin "7") (pinfunction "VCC_7") (pintype "passive"))
    )
    (net (code "10") (name "/16U2PROG_328P_RESETn") (class "Default")
      (node (ref "JP1") (pin "2") (pinfunction "2_2") (pintype "passive"))
      (node (ref "R1") (pin "1") (pinfunction "1_1") (pintype "passive"))
      (node (ref "U2") (pin "13") (pinfunction "~{CT}S_/~{_HWB}_/_T0_/_AIN6_/_INT7_/_PD7_13") (pintype "passive"))
    )
    (net (code "11") (name "/16U2_16MHZ_XTAL1") (class "Default")
      (node (ref "C10") (pin "2") (pinfunction "2_2") (pintype "passive"))
      (node (ref "R9") (pin "1") (pinfunction "1_1") (pintype "passive"))
      (node (ref "U2") (pin "1") (pinfunction "XTAL1_1") (pintype "passive"))
      (node (ref "Y2") (pin "1") (pinfunction "1_1") (pintype "passive"))
    )
    (net (code "12") (name "/16U2_16MHZ_XTAL2") (class "Default")
      (node (ref "C9") (pin "2") (pinfunction "2_2") (pintype "passive"))
      (node (ref "R9") (pin "2") (pinfunction "2_2") (pintype "passive"))
      (node (ref "U2") (pin "2") (pinfunction "XTAL2_/_PC0_2") (pintype "passive"))
      (node (ref "Y2") (pin "2") (pinfunction "2_2") (pintype "passive"))
    )
    (net (code "13") (name "/16U2_BUF_RESETn") (class "Default")
      (node (ref "C31") (pin "2") (pinfunction "2_2") (pintype "passive"))
      (node (ref "R23") (pin "2") (pinfunction "2_2") (pintype "passive"))
      (node (ref "U5") (pin "1") (pinfunction "1_1") (pintype "passive"))
      (node (ref "U5") (pin "2") (pinfunction "2_2") (pintype "passive"))
    )
    (net (code "14") (name "/16U2_HDR_RESETn") (class "Default")
      (node (ref "J6") (pin "5") (pinfunction "5_5") (pintype "passive"))
      (node (ref "JP3") (pin "3") (pinfunction "3_3") (pintype "passive"))
    )
    (net (code "15") (name "/16U2_MISO") (class "Default")
      (node (ref "J6") (pin "1") (pinfunction "1_1") (pintype "passive"))
      (node (ref "U2") (pin "17") (pinfunction "PDO_/_MISO_/_PCINT3_/_PB3_17") (pintype "passive"))
    )
    (net (code "16") (name "/16U2_MOSI") (class "Default")
      (node (ref "J6") (pin "4") (pinfunction "4_4") (pintype "passive"))
      (node (ref "U2") (pin "16") (pinfunction "PDI_/_MOSI_/_PCINT2_/_PB2_16") (pintype "passive"))
    )
    (net (code "17") (name "/16U2_PB4") (class "Default")
      (node (ref "JP2") (pin "1") (pinfunction "1_1") (pintype "passive"))
      (node (ref "JP3") (pin "2") (pinfunction "2_2") (pintype "passive"))
      (node (ref "U2") (pin "18") (pinfunction "T1_/_PCINT4_/_PB4_18") (pintype "passive"))
    )
    (net (code "18") (name "/16U2_PB5") (class "Default")
      (node (ref "JP2") (pin "3") (pinfunction "3_3") (pintype "passive"))
      (node (ref "U2") (pin "19") (pinfunction "PCINT5_/_PB5_19") (pintype "passive"))
    )
    (net (code "19") (name "/16U2_PB6") (class "Default")
      (node (ref "JP2") (pin "2") (pinfunction "2_2") (pintype "passive"))
      (node (ref "U2") (pin "20") (pinfunction "PCINT6_/_PB6_20") (pintype "passive"))
    )
    (net (code "20") (name "/16U2_PB7") (class "Default")
      (node (ref "JP2") (pin "4") (pinfunction "4_4") (pintype "passive"))
      (node (ref "U2") (pin "21") (pinfunction "OC.0A_/_OC.1C_/_PCINT7_/_PB7_21") (pintype "passive"))
    )
    (net (code "21") (name "/16U2_RESETn") (class "Default")
      (node (ref "JP3") (pin "4") (pinfunction "4_4") (pintype "passive"))
      (node (ref "R4") (pin "1") (pinfunction "1_1") (pintype "passive"))
      (node (ref "U2") (pin "24") (pinfunction "PC1_/~{_RESET}_/_DW_24") (pintype "passive"))
      (node (ref "U5") (pin "4") (pinfunction "4_4") (pintype "passive"))
    )
    (net (code "22") (name "/16U2_RXD") (class "Default")
      (node (ref "R11") (pin "1") (pinfunction "1_1") (pintype "passive"))
      (node (ref "U2") (pin "8") (pinfunction "RXD1_/_AIN1_/_INT2_/_PD2_8") (pintype "passive"))
    )
    (net (code "23") (name "/16U2_RX_LED") (class "Default")
      (node (ref "D4") (pin "1") (pinfunction "Cathode_1") (pintype "passive"))
      (node (ref "U2") (pin "10") (pinfunction "AIN3_/_INT5_/_PD4_10") (pintype "passive"))
    )
    (net (code "24") (name "/16U2_SCLK") (class "Default")
      (node (ref "J6") (pin "3") (pinfunction "3_3") (pintype "passive"))
      (node (ref "R5") (pin "2") (pinfunction "2_2") (pintype "passive"))
    )
    (net (code "25") (name "/16U2_SCLK_R") (class "Default")
      (node (ref "R5") (pin "1") (pinfunction "1_1") (pintype "passive"))
      (node (ref "U2") (pin "15") (pinfunction "SCLK_/_PCINT1_/_PB1_15") (pintype "passive"))
    )
    (net (code "26") (name "/16U2_TXD") (class "Default")
      (node (ref "R10") (pin "1") (pinfunction "1_1") (pintype "passive"))
      (node (ref "U2") (pin "9") (pinfunction "TXD1_/_INT3_/_PD3_9") (pintype "passive"))
    )
    (net (code "27") (name "/16U2_TX_LED") (class "Default")
      (node (ref "D3") (pin "1") (pinfunction "Cathode_1") (pintype "passive"))
      (node (ref "U2") (pin "11") (pinfunction "XCK_/_AIN4_/_PCINT12_/_PD5_11") (pintype "passive"))
    )
    (net (code "28") (name "/328P_16MHZ_XTAL1") (class "Default")
      (node (ref "C27") (pin "2") (pinfunction "2_2") (pintype "passive"))
      (node (ref "R16") (pin "1") (pinfunction "1_1") (pintype "passive"))
      (node (ref "U1") (pin "9") (pinfunction "PB6_/_PCINT6_/_TOSC1_/_XTAL1_9") (pintype "passive"))
      (node (ref "Y1") (pin "1") (pinfunction "1_1") (pintype "passive"))
    )
    (net (code "29") (name "/328P_16MHZ_XTAL2") (class "Default")
      (node (ref "C25") (pin "2") (pinfunction "2_2") (pintype "passive"))
      (node (ref "R16") (pin "2") (pinfunction "2_2") (pintype "passive"))
      (node (ref "U1") (pin "10") (pinfunction "PB7_/_PCINT7_/_TOSC2_/_XTAL2_10") (pintype "passive"))
      (node (ref "Y1") (pin "2") (pinfunction "2_2") (pintype "passive"))
    )
    (net (code "30") (name "/328P_AUTORESETn") (class "Default")
      (node (ref "C11") (pin "1") (pinfunction "1_1") (pintype "passive"))
      (node (ref "R18") (pin "1") (pinfunction "1_1") (pintype "passive"))
      (node (ref "U6") (pin "1") (pinfunction "1_1") (pintype "passive"))
    )
    (net (code "31") (name "/328P_BUF_RESETn") (class "Default")
      (node (ref "C32") (pin "2") (pinfunction "2_2") (pintype "passive"))
      (node (ref "R24") (pin "2") (pinfunction "2_2") (pintype "passive"))
      (node (ref "U6") (pin "2") (pinfunction "2_2") (pintype "passive"))
    )
    (net (code "32") (name "/328P_RESETn") (class "Default")
      (node (ref "J1") (pin "3") (pinfunction "3_3") (pintype "passive"))
      (node (ref "J5") (pin "5") (pinfunction "5_5") (pintype "passive"))
      (node (ref "JP3") (pin "1") (pinfunction "1_1") (pintype "passive"))
      (node (ref "R14") (pin "2") (pinfunction "2_2") (pintype "passive"))
      (node (ref "U1") (pin "1") (pinfunction "PC6_/_PCINT14_/~{_RESET}_1") (pintype "passive"))
      (node (ref "U6") (pin "4") (pinfunction "4_4") (pintype "passive"))
    )
    (net (code "33") (name "/AD0") (class "Default")
      (node (ref "J2") (pin "1") (pinfunction "1_1") (pintype "passive"))
      (node (ref "U1") (pin "23") (pinfunction "PCINT8_/_ADC0_/_PC0_23") (pintype "passive"))
    )
    (net (code "34") (name "/AD1") (class "Default")
      (node (ref "J2") (pin "2") (pinfunction "2_2") (pintype "passive"))
      (node (ref "U1") (pin "24") (pinfunction "PCINT9_/_ADC1_/_PC1_24") (pintype "passive"))
    )
    (net (code "35") (name "/AD2") (class "Default")
      (node (ref "J2") (pin "3") (pinfunction "3_3") (pintype "passive"))
      (node (ref "U1") (pin "25") (pinfunction "PCINT10_/_ADC2_/_PC2_25") (pintype "passive"))
    )
    (net (code "36") (name "/AD3") (class "Default")
      (node (ref "J2") (pin "4") (pinfunction "4_4") (pintype "passive"))
      (node (ref "U1") (pin "26") (pinfunction "PCINT11_/_ADC3_/_PC3_26") (pintype "passive"))
    )
    (net (code "37") (name "/AD4{slash}SDA") (class "Default")
      (node (ref "J2") (pin "5") (pinfunction "5_5") (pintype "passive"))
      (node (ref "J4") (pin "9") (pinfunction "9_9") (pintype "passive"))
      (node (ref "U1") (pin "27") (pinfunction "SDA_/_PCINT12_/_ADC4_/_PC4_27") (pintype "passive"))
    )
    (net (code "38") (name "/AD5{slash}SCL") (class "Default")
      (node (ref "J2") (pin "6") (pinfunction "6_6") (pintype "passive"))
      (node (ref "J4") (pin "10") (pinfunction "10_10") (pintype "passive"))
      (node (ref "U1") (pin "28") (pinfunction "SCL_/_PCINT13_/_ADC5_/_PC5_28") (pintype "passive"))
    )
    (net (code "39") (name "/BUTTON_RESETn") (class "Default")
      (node (ref "D6") (pin "2") (pinfunction "Anode_2") (pintype "passive"))
      (node (ref "R20") (pin "1") (pinfunction "1_1") (pintype "passive"))
      (node (ref "R24") (pin "1") (pinfunction "1_1") (pintype "passive"))
      (node (ref "SW1") (pin "1") (pinfunction "1_1") (pintype "passive"))
      (node (ref "SW1") (pin "2") (pinfunction "2_2") (pintype "passive"))
    )
    (net (code "40") (name "/CON_UBS_N") (class "Default")
      (node (ref "J7") (pin "2") (pinfunction "2_2") (pintype "passive"))
      (node (ref "R6") (pin "1") (pinfunction "1_1") (pintype "passive"))
      (node (ref "Z1") (pin "2") (pinfunction "2_2") (pintype "passive"))
    )
    (net (code "41") (name "/CON_USB_P") (class "Default")
      (node (ref "J7") (pin "3") (pinfunction "3_3") (pintype "passive"))
      (node (ref "R7") (pin "1") (pinfunction "1_1") (pintype "passive"))
      (node (ref "Z2") (pin "2") (pinfunction "2_2") (pintype "passive"))
    )
    (net (code "42") (name "/IO0") (class "Default")
      (node (ref "J3") (pin "1") (pinfunction "1_1") (pintype "passive"))
      (node (ref "R10") (pin "2") (pinfunction "2_2") (pintype "passive"))
      (node (ref "U1") (pin "2") (pinfunction "RXD_/_PCINT16_/_PD0_2") (pintype "passive"))
    )
    (net (code "43") (name "/IO1") (class "Default")
      (node (ref "J3") (pin "2") (pinfunction "2_2") (pintype "passive"))
      (node (ref "R11") (pin "2") (pinfunction "2_2") (pintype "passive"))
      (node (ref "U1") (pin "3") (pinfunction "TXD_/_PCINT17_/_PD1_3") (pintype "passive"))
    )
    (net (code "44") (name "/IO2") (class "Default")
      (node (ref "J3") (pin "3") (pinfunction "3_3") (pintype "passive"))
      (node (ref "U1") (pin "4") (pinfunction "INT0_/_PCINT18_/_PD2_4") (pintype "passive"))
    )
    (net (code "45") (name "/IO3") (class "Default")
      (node (ref "J3") (pin "4") (pinfunction "4_4") (pintype "passive"))
      (node (ref "U1") (pin "5") (pinfunction "OC2B_/_INT1_/_PCINT19_/_PD3_5") (pintype "passive"))
    )
    (net (code "46") (name "/IO4") (class "Default")
      (node (ref "J3") (pin "5") (pinfunction "5_5") (pintype "passive"))
      (node (ref "U1") (pin "6") (pinfunction "XCK_/_T0_/_PCINT20_/_PD4_6") (pintype "passive"))
    )
    (net (code "47") (name "/IO5") (class "Default")
      (node (ref "J3") (pin "6") (pinfunction "6_6") (pintype "passive"))
      (node (ref "U1") (pin "11") (pinfunction "OC0B_/_T1_/_PCINT21_/_PD5_11") (pintype "passive"))
    )
    (net (code "48") (name "/IO6") (class "Default")
      (node (ref "J3") (pin "7") (pinfunction "7_7") (pintype "passive"))
      (node (ref "U1") (pin "12") (pinfunction "OC0A_/_AIN0_/_PCINT22_/_PD6_12") (pintype "passive"))
    )
    (net (code "49") (name "/IO7") (class "Default")
      (node (ref "J3") (pin "8") (pinfunction "8_8") (pintype "passive"))
      (node (ref "U1") (pin "13") (pinfunction "AIN1_/_PCINT23_/_PD7_13") (pintype "passive"))
    )
    (net (code "50") (name "/IO8") (class "Default")
      (node (ref "J4") (pin "1") (pinfunction "1_1") (pintype "passive"))
      (node (ref "R22") (pin "2") (pinfunction "2_2") (pintype "passive"))
      (node (ref "U1") (pin "14") (pinfunction "CLKO_/_ICP1_/_PCINT0_/_PB0_14") (pintype "passive"))
    )
    (net (code "51") (name "/IO9") (class "Default")
      (node (ref "J4") (pin "2") (pinfunction "2_2") (pintype "passive"))
      (node (ref "U1") (pin "15") (pinfunction "OC1A_/_PCINT1_/_PB1_15") (pintype "passive"))
    )
    (net (code "52") (name "/MISO") (class "Default")
      (node (ref "J4") (pin "5") (pinfunction "5_5") (pintype "passive"))
      (node (ref "J5") (pin "1") (pinfunction "1_1") (pintype "passive"))
      (node (ref "U1") (pin "18") (pinfunction "MISO_/_PCINT4_/_PB4_18") (pintype "passive"))
    )
    (net (code "53") (name "/MOSI") (class "Default")
      (node (ref "J4") (pin "4") (pinfunction "4_4") (pintype "passive"))
      (node (ref "J5") (pin "4") (pinfunction "4_4") (pintype "passive"))
      (node (ref "U1") (pin "17") (pinfunction "MOSI_/_OC2A_/_PCINT3_/_PB3_17") (pintype "passive"))
    )
    (net (code "54") (name "/SCK") (class "Default")
      (node (ref "J4") (pin "6") (pinfunction "6_6") (pintype "passive"))
      (node (ref "J5") (pin "3") (pinfunction "3_3") (pintype "passive"))
      (node (ref "R13") (pin "2") (pinfunction "2_2") (pintype "passive"))
      (node (ref "U4") (pin "1") (pinfunction "1_1") (pintype "passive"))
      (node (ref "U4") (pin "2") (pinfunction "2_2") (pintype "passive"))
    )
    (net (code "55") (name "/SCK_R") (class "Default")
      (node (ref "R13") (pin "1") (pinfunction "1_1") (pintype "passive"))
      (node (ref "U1") (pin "19") (pinfunction "SCK_/_PCINT5_/_PB5_19") (pintype "passive"))
    )
    (net (code "56") (name "/SS") (class "Default")
      (node (ref "J4") (pin "3") (pinfunction "3_3") (pintype "passive"))
      (node (ref "U1") (pin "16") (pinfunction "~{SS}_/_OC1B_/_PCINT2_/_PB2_16") (pintype "passive"))
    )
    (net (code "57") (name "/USB_N") (class "Default")
      (node (ref "R6") (pin "2") (pinfunction "2_2") (pintype "passive"))
      (node (ref "U2") (pin "30") (pinfunction "D-_30") (pintype "passive"))
    )
    (net (code "58") (name "/USB_P") (class "Default")
      (node (ref "R7") (pin "2") (pinfunction "2_2") (pintype "passive"))
      (node (ref "U2") (pin "29") (pinfunction "D+_29") (pintype "passive"))
    )
    (net (code "59") (name "/USER_ BUTTON") (class "Default")
      (node (ref "R21") (pin "1") (pinfunction "1_1") (pintype "passive"))
      (node (ref "R25") (pin "1") (pinfunction "1_1") (pintype "passive"))
      (node (ref "SW2") (pin "1") (pinfunction "1_1") (pintype "passive"))
      (node (ref "SW2") (pin "2") (pinfunction "2_2") (pintype "passive"))
    )
    (net (code "60") (name "/USER_BUTTON_BUF") (class "Default")
      (node (ref "C33") (pin "2") (pinfunction "2_2") (pintype "passive"))
      (node (ref "R25") (pin "2") (pinfunction "2_2") (pintype "passive"))
      (node (ref "U7") (pin "1") (pinfunction "1_1") (pintype "passive"))
      (node (ref "U7") (pin "2") (pinfunction "2_2") (pintype "passive"))
    )
    (net (code "61") (name "GND") (class "Default")
      (node (ref "C1") (pin "2") (pinfunction "2_2") (pintype "passive"))
      (node (ref "C10") (pin "1") (pinfunction "1_1") (pintype "passive"))
      (node (ref "C12") (pin "1") (pinfunction "1_1") (pintype "passive"))
      (node (ref "C13") (pin "1") (pinfunction "1_1") (pintype "passive"))
      (node (ref "C14") (pin "1") (pinfunction "1_1") (pintype "passive"))
      (node (ref "C15") (pin "1") (pinfunction "1_1") (pintype "passive"))
      (node (ref "C16") (pin "1") (pinfunction "1_1") (pintype "passive"))
      (node (ref "C17") (pin "1") (pinfunction "1_1") (pintype "passive"))
      (node (ref "C19") (pin "1") (pinfunction "1_1") (pintype "passive"))
      (node (ref "C2") (pin "2") (pinfunction "2_2") (pintype "passive"))
      (node (ref "C20") (pin "1") (pinfunction "1_1") (pintype "passive"))
      (node (ref "C21") (pin "1") (pinfunction "1_1") (pintype "passive"))
      (node (ref "C22") (pin "1") (pinfunction "1_1") (pintype "passive"))
      (node (ref "C23") (pin "1") (pinfunction "1_1") (pintype "passive"))
      (node (ref "C24") (pin "1") (pinfunction "1_1") (pintype "passive"))
      (node (ref "C25") (pin "1") (pinfunction "1_1") (pintype "passive"))
      (node (ref "C26") (pin "1") (pinfunction "1_1") (pintype "passive"))
      (node (ref "C27") (pin "1") (pinfunction "1_1") (pintype "passive"))
      (node (ref "C28") (pin "1") (pinfunction "1_1") (pintype "passive"))
      (node (ref "C29") (pin "1") (pinfunction "1_1") (pintype "passive"))
      (node (ref "C3") (pin "1") (pinfunction "1_1") (pintype "passive"))
      (node (ref "C30") (pin "1") (pinfunction "1_1") (pintype "passive"))
      (node (ref "C31") (pin "1") (pinfunction "1_1") (pintype "passive"))
      (node (ref "C32") (pin "1") (pinfunction "1_1") (pintype "passive"))
      (node (ref "C33") (pin "1") (pinfunction "1_1") (pintype "passive"))
      (node (ref "C34") (pin "1") (pinfunction "1_1") (pintype "passive"))
      (node (ref "C4") (pin "1") (pinfunction "1_1") (pintype "passive"))
      (node (ref "C5") (pin "1") (pinfunction "1_1") (pintype "passive"))
      (node (ref "C6") (pin "1") (pinfunction "1_1") (pintype "passive"))
      (node (ref "C7") (pin "1") (pinfunction "1_1") (pintype "passive"))
      (node (ref "C8") (pin "1") (pinfunction "1_1") (pintype "passive"))
      (node (ref "C9") (pin "1") (pinfunction "1_1") (pintype "passive"))
      (node (ref "D1") (pin "1") (pinfunction "Cathode_1") (pintype "passive"))
      (node (ref "J1") (pin "6") (pinfunction "6_6") (pintype "passive"))
      (node (ref "J1") (pin "7") (pinfunction "7_7") (pintype "passive"))
      (node (ref "J4") (pin "7") (pinfunction "7_7") (pintype "passive"))
      (node (ref "J5") (pin "6") (pinfunction "6_6") (pintype "passive"))
      (node (ref "J6") (pin "6") (pinfunction "6_6") (pintype "passive"))
      (node (ref "J7") (pin "10") (pinfunction "10_10") (pintype "passive"))
      (node (ref "J7") (pin "11") (pinfunction "11_11") (pintype "passive"))
      (node (ref "J7") (pin "5") (pinfunction "5_5") (pintype "passive"))
      (node (ref "J7") (pin "6") (pinfunction "6_6") (pintype "passive"))
      (node (ref "J7") (pin "7") (pinfunction "7_7") (pintype "passive"))
      (node (ref "J7") (pin "8") (pinfunction "8_8") (pintype "passive"))
      (node (ref "J7") (pin "9") (pinfunction "9_9") (pintype "passive"))
      (node (ref "J9") (pin "1") (pinfunction "1_1") (pintype "passive"))
      (node (ref "MH1") (pin "1") (pinfunction "1_1") (pintype "passive"))
      (node (ref "MH2") (pin "1") (pinfunction "1_1") (pintype "passive"))
      (node (ref "MH3") (pin "1") (pinfunction "1_1") (pintype "passive"))
      (node (ref "R12") (pin "1") (pinfunction "1_1") (pintype "passive"))
      (node (ref "R8") (pin "2") (pinfunction "2_2") (pintype "passive"))
      (node (ref "SW1") (pin "3") (pinfunction "3_3") (pintype "passive"))
      (node (ref "SW1") (pin "4") (pinfunction "4_4") (pintype "passive"))
      (node (ref "SW2") (pin "3") (pinfunction "3_3") (pintype "passive"))
      (node (ref "SW2") (pin "4") (pinfunction "4_4") (pintype "passive"))
      (node (ref "U1") (pin "22") (pinfunction "GND_2_22") (pintype "passive"))
      (node (ref "U1") (pin "8") (pinfunction "GND_1_8") (pintype "passive"))
      (node (ref "U2") (pin "28") (pinfunction "UGND_28") (pintype "passive"))
      (node (ref "U2") (pin "3") (pinfunction "GND_3") (pintype "passive"))
      (node (ref "U3") (pin "3") (pinfunction "GND_3") (pintype "passive"))
      (node (ref "U3") (pin "6") (pinfunction "EPAD_6") (pintype "passive"))
      (node (ref "U4") (pin "3") (pinfunction "3_3") (pintype "passive"))
      (node (ref "U5") (pin "3") (pinfunction "3_3") (pintype "passive"))
      (node (ref "U6") (pin "3") (pinfunction "3_3") (pintype "passive"))
      (node (ref "U7") (pin "3") (pinfunction "3_3") (pintype "passive"))
      (node (ref "Z1") (pin "1") (pinfunction "1_1") (pintype "passive"))
      (node (ref "Z2") (pin "1") (pinfunction "1_1") (pintype "passive"))
    )
    (net (code "62") (name "Net-(C11-Pad2)") (class "Default")
      (node (ref "C11") (pin "2") (pinfunction "2_2") (pintype "passive"))
      (node (ref "JP1") (pin "1") (pinfunction "1_1") (pintype "passive"))
    )
    (net (code "63") (name "Net-(D1-Anode)") (class "Default")
      (node (ref "D1") (pin "2") (pinfunction "Anode_2") (pintype "passive"))
      (node (ref "R17") (pin "1") (pinfunction "1_1") (pintype "passive"))
    )
    (net (code "64") (name "Net-(D2-Anode)") (class "Default")
      (node (ref "D2") (pin "2") (pinfunction "Anode_2") (pintype "passive"))
      (node (ref "R15") (pin "1") (pinfunction "1_1") (pintype "passive"))
    )
    (net (code "65") (name "Net-(D2-Cathode)") (class "Default")
      (node (ref "D2") (pin "1") (pinfunction "Cathode_1") (pintype "passive"))
      (node (ref "U4") (pin "4") (pinfunction "4_4") (pintype "passive"))
    )
    (net (code "66") (name "Net-(D3-Anode)") (class "Default")
      (node (ref "D3") (pin "2") (pinfunction "Anode_2") (pintype "passive"))
      (node (ref "R2") (pin "1") (pinfunction "1_1") (pintype "passive"))
    )
    (net (code "67") (name "Net-(D4-Anode)") (class "Default")
      (node (ref "D4") (pin "2") (pinfunction "Anode_2") (pintype "passive"))
      (node (ref "R3") (pin "1") (pinfunction "1_1") (pintype "passive"))
    )
    (net (code "68") (name "Net-(D5-Anode)") (class "Default")
      (node (ref "D5") (pin "2") (pinfunction "Anode_2") (pintype "passive"))
      (node (ref "R19") (pin "1") (pinfunction "1_1") (pintype "passive"))
      (node (ref "R23") (pin "1") (pinfunction "1_1") (pintype "passive"))
    )
    (net (code "69") (name "Net-(J7-Pad4)") (class "Default")
      (node (ref "J7") (pin "4") (pinfunction "4_4") (pintype "passive"))
      (node (ref "R8") (pin "1") (pinfunction "1_1") (pintype "passive"))
    )
    (net (code "70") (name "Net-(JP1-Pad3)") (class "Default")
      (node (ref "JP1") (pin "3") (pinfunction "3_3") (pintype "passive"))
      (node (ref "R12") (pin "2") (pinfunction "2_2") (pintype "passive"))
    )
    (net (code "71") (name "Net-(R22-Pad1)") (class "Default")
      (node (ref "R22") (pin "1") (pinfunction "1_1") (pintype "passive"))
      (node (ref "U7") (pin "4") (pinfunction "4_4") (pintype "passive"))
    )
    (net (code "72") (name "unconnected-(J1-Pad1)") (class "Default")
      (node (ref "J1") (pin "1") (pinfunction "1_1") (pintype "passive+no_connect"))
    )
    (net (code "73") (name "unconnected-(J1-Pad8)") (class "Default")
      (node (ref "J1") (pin "8") (pinfunction "8_8") (pintype "passive+no_connect"))
    )
    (net (code "74") (name "unconnected-(MH4-Pad1)") (class "Default")
      (node (ref "MH4") (pin "1") (pinfunction "1_1") (pintype "passive+no_connect"))
    )
    (net (code "75") (name "unconnected-(U2-AIN0_{slash}_INT1_{slash}_PD1-Pad7)") (class "Default")
      (node (ref "U2") (pin "7") (pinfunction "AIN0_/_INT1_/_PD1_7") (pintype "passive+no_connect"))
    )
    (net (code "76") (name "unconnected-(U2-AIN2_{slash}_PCINT11_{slash}_PC2-Pad5)") (class "Default")
      (node (ref "U2") (pin "5") (pinfunction "AIN2_/_PCINT11_/_PC2_5") (pintype "passive+no_connect"))
    )
    (net (code "77") (name "unconnected-(U2-CLKO_{slash}_ICP1_{slash}_INT4_{slash}_PC7-Pad22)") (class "Default")
      (node (ref "U2") (pin "22") (pinfunction "CLKO_/_ICP1_/_INT4_/_PC7_22") (pintype "passive+no_connect"))
    )
    (net (code "78") (name "unconnected-(U2-OC.0B_{slash}_INT0_{slash}_PD0-Pad6)") (class "Default")
      (node (ref "U2") (pin "6") (pinfunction "OC.0B_/_INT0_/_PD0_6") (pintype "passive+no_connect"))
    )
    (net (code "79") (name "unconnected-(U2-OC.1A_{slash}_PCINT8_{slash}_PC6-Pad23)") (class "Default")
      (node (ref "U2") (pin "23") (pinfunction "OC.1A_/_PCINT8_/_PC6_23") (pintype "passive+no_connect"))
    )
    (net (code "80") (name "unconnected-(U2-OC.1B_{slash}_PCINT9_{slash}_PC5-Pad25)") (class "Default")
      (node (ref "U2") (pin "25") (pinfunction "OC.1B_/_PCINT9_/_PC5_25") (pintype "passive+no_connect"))
    )
    (net (code "81") (name "unconnected-(U2-PCINT10_{slash}_PC4-Pad26)") (class "Default")
      (node (ref "U2") (pin "26") (pinfunction "PCINT10_/_PC4_26") (pintype "passive+no_connect"))
    )
    (net (code "82") (name "unconnected-(U2-~{RTS}_{slash}_AIN5_{slash}_INT6_{slash}_PD6-Pad12)") (class "Default")
      (node (ref "U2") (pin "12") (pinfunction "~{RTS}_/_AIN5_/_INT6_/_PD6_12") (pintype "passive+no_connect"))
    )
    (net (code "83") (name "unconnected-(U2-~{SS}_{slash}_PCINT0_{slash}_PB0-Pad14)") (class "Default")
      (node (ref "U2") (pin "14") (pinfunction "~{SS}_/_PCINT0_/_PB0_14") (pintype "passive+no_connect"))
    )
  )
)
